# programmer.net
KiCad netlist of a schematic drawn in Altium Designer
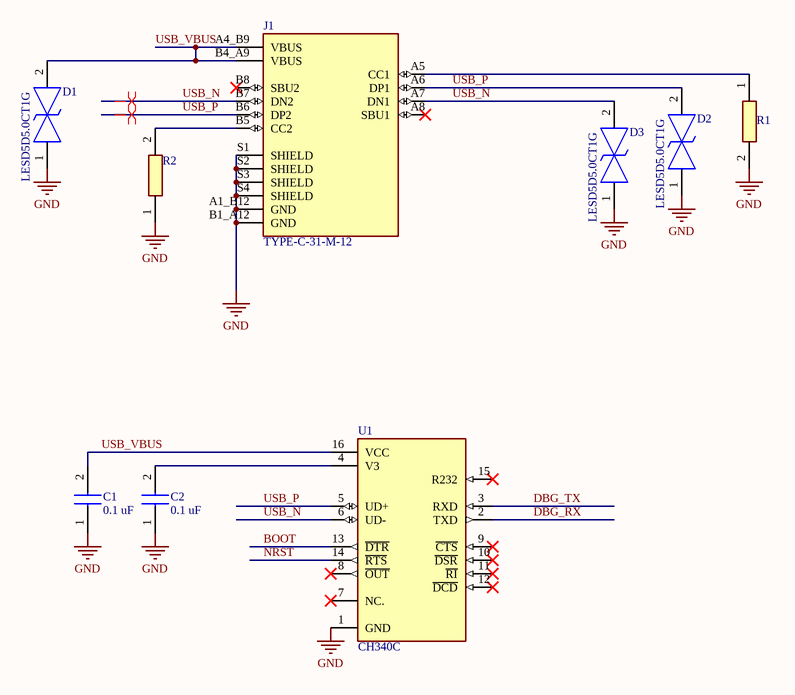
[diagram p0: programmer.SchDoc]

(export (version "E")
  (design (tool "Eeschema 10.0.6"))
  (components
    (comp (ref "C1")
      (value "0.1 uF")
      (footprint "CAP0603")
      (description "Capacitor")
      (fields
        (field (name "MANUFACTURER_PART_NUMBER") "CC0603KRX7R9BB104")
        (field (name "MOUSER PART NUMBER") "603-CC603KRX7R9BB104")
      )
      (libsource (lib "Valve_Controller_Lib") (part "CC0603KRX7R9BB104"))
    )
    (comp (ref "C2")
      (value "0.1 uF")
      (footprint "CAP0603")
      (description "Capacitor")
      (fields
        (field (name "MANUFACTURER_PART_NUMBER") "CC0603KRX7R9BB104")
        (field (name "MOUSER PART NUMBER") "603-CC603KRX7R9BB104")
      )
      (libsource (lib "Valve_Controller_Lib") (part "CC0603KRX7R9BB104"))
    )
    (comp (ref "D1")
      (value "LESD5D5.0CT1G")
      (footprint "SamacSys:LESD5D50CT1G")
      (description "TVS Diode (Bi-directional)")
      (libsource (lib "*") (part "LESD5D5.0CT1G"))
    )
    (comp (ref "D2")
      (value "LESD5D5.0CT1G")
      (footprint "SamacSys:LESD5D50CT1G")
      (description "TVS Diode (Bi-directional)")
      (libsource (lib "*") (part "LESD5D5.0CT1G"))
    )
    (comp (ref "D3")
      (value "LESD5D5.0CT1G")
      (footprint "SamacSys:LESD5D50CT1G")
      (description "TVS Diode (Bi-directional)")
      (libsource (lib "*") (part "LESD5D5.0CT1G"))
    )
    (comp (ref "J1")
      (value "TYPE-C-31-M-12")
      (footprint "HRO_TYPE-C-31-M-12")
      (description "USB Connectors 24 Receptacle 1 8.94*7.3mm RoHS")
      (fields (field (name "MF") "HRO Electronics Co., Ltd."))
      (libsource (lib "TYPE-C-31-M-12") (part "TYPE-C-31-M-12"))
    )
    (comp (ref "R1")
      (value "CRCW0402100KFKEDHP")
      (footprint "RESC1005X40N")
      (description "Resistor")
      (fields (field (name "MOUSER PART NUMBER") "71-CRCW0402100KFKEDH"))
      (libsource (lib "") (part "CRCW0402100KFKEDHP_1"))
    )
    (comp (ref "R2")
      (value "CRCW0402100KFKEDHP")
      (footprint "RESC1005X40N")
      (description "Resistor")
      (fields (field (name "MOUSER PART NUMBER") "71-CRCW0402100KFKEDH"))
      (libsource (lib "Valve_Controller_Lib") (part "CRCW0402100KFKEDHP"))
    )
    (comp (ref "U1")
      (value "CH340C")
      (footprint "SOIC127P600X180-16N")
      (description "USB to serial chip CH340")
      (fields (field (name "MF") "WCH"))
      (libsource (lib "CH340C") (part "CH340C"))
    )
  )
  (nets
    (net (code "1") (name "/BOOT") (class "Default")
      (node (ref "U1") (pin "13") (pinfunction "~{DTR}_13") (pintype "output"))
    )
    (net (code "2") (name "/DBG_RX") (class "Default")
      (node (ref "U1") (pin "2") (pinfunction "TXD_2") (pintype "output"))
    )
    (net (code "3") (name "/DBG_TX") (class "Default")
      (node (ref "U1") (pin "3") (pinfunction "RXD_3") (pintype "input"))
    )
    (net (code "4") (name "/NRST") (class "Default")
      (node (ref "U1") (pin "14") (pinfunction "~{RTS}_14") (pintype "output"))
    )
    (net (code "5") (name "/USB_N") (class "Default")
      (node (ref "D3") (pin "2") (pinfunction "2_2") (pintype "passive"))
      (node (ref "J1") (pin "A7") (pinfunction "DN1_A7") (pintype "bidirectional"))
      (node (ref "J1") (pin "B7") (pinfunction "DN2_B7") (pintype "bidirectional"))
      (node (ref "U1") (pin "6") (pinfunction "UD-_6") (pintype "bidirectional"))
    )
    (net (code "6") (name "/USB_P") (class "Default")
      (node (ref "D2") (pin "2") (pinfunction "2_2") (pintype "passive"))
      (node (ref "J1") (pin "A6") (pinfunction "DP1_A6") (pintype "bidirectional"))
      (node (ref "J1") (pin "B6") (pinfunction "DP2_B6") (pintype "bidirectional"))
      (node (ref "U1") (pin "5") (pinfunction "UD+_5") (pintype "bidirectional"))
    )
    (net (code "7") (name "/USB_VBUS") (class "Default")
      (node (ref "C1") (pin "2") (pinfunction "2_2") (pintype "passive"))
      (node (ref "D1") (pin "2") (pinfunction "2_2") (pintype "passive"))
      (node (ref "J1") (pin "A4_B9") (pinfunction "VBUS_A4_B9") (pintype "power_in"))
      (node (ref "J1") (pin "B4_A9") (pinfunction "VBUS_B4_A9") (pintype "power_in"))
      (node (ref "U1") (pin "16") (pinfunction "VCC_16") (pintype "power_in"))
    )
    (net (code "8") (name "GND") (class "Default")
      (node (ref "C1") (pin "1") (pinfunction "1_1") (pintype "passive"))
      (node (ref "C2") (pin "1") (pinfunction "1_1") (pintype "passive"))
      (node (ref "D1") (pin "1") (pinfunction "1_1") (pintype "passive"))
      (node (ref "D2") (pin "1") (pinfunction "1_1") (pintype "passive"))
      (node (ref "D3") (pin "1") (pinfunction "1_1") (pintype "passive"))
      (node (ref "J1") (pin "A1_B12") (pinfunction "GND_A1_B12") (pintype "power_in"))
      (node (ref "J1") (pin "B1_A12") (pinfunction "GND_B1_A12") (pintype "power_in"))
      (node (ref "J1") (pin "S1") (pinfunction "SHIELD_S1") (pintype "passive"))
      (node (ref "J1") (pin "S2") (pinfunction "SHIELD_S2") (pintype "passive"))
      (node (ref "J1") (pin "S3") (pinfunction "SHIELD_S3") (pintype "passive"))
      (node (ref "J1") (pin "S4") (pinfunction "SHIELD_S4") (pintype "passive"))
      (node (ref "R1") (pin "2") (pinfunction "2_2") (pintype "passive"))
      (node (ref "R2") (pin "1") (pinfunction "1_1") (pintype "passive"))
      (node (ref "U1") (pin "1") (pinfunction "GND_1") (pintype "power_in"))
    )
    (net (code "9") (name "Net-(J1-CC1)") (class "Default")
      (node (ref "J1") (pin "A5") (pinfunction "CC1_A5") (pintype "bidirectional"))
      (node (ref "R1") (pin "1") (pinfunction "1_1") (pintype "passive"))
    )
    (net (code "10") (name "Net-(J1-CC2)") (class "Default")
      (node (ref "J1") (pin "B5") (pinfunction "CC2_B5") (pintype "bidirectional"))
      (node (ref "R2") (pin "2") (pinfunction "2_2") (pintype "passive"))
    )
    (net (code "11") (name "Net-(U1-V3)") (class "Default")
      (node (ref "C2") (pin "2") (pinfunction "2_2") (pintype "passive"))
      (node (ref "U1") (pin "4") (pinfunction "V3_4") (pintype "power_in"))
    )
    (net (code "12") (name "unconnected-(J1-SBU1-PadA8)") (class "Default")
      (node (ref "J1") (pin "A8") (pinfunction "SBU1_A8") (pintype "bidirectional+no_connect"))
    )
    (net (code "13") (name "unconnected-(J1-SBU2-PadB8)") (class "Default")
      (node (ref "J1") (pin "B8") (pinfunction "SBU2_B8") (pintype "bidirectional+no_connect"))
    )
    (net (code "14") (name "unconnected-(U1-NC.-Pad7)") (class "Default")
      (node (ref "U1") (pin "7") (pinfunction "NC._7") (pintype "passive+no_connect"))
    )
    (net (code "15") (name "unconnected-(U1-R232-Pad15)") (class "Default")
      (node (ref "U1") (pin "15") (pinfunction "R232_15") (pintype "input+no_connect"))
    )
    (net (code "16") (name "unconnected-(U1-~{CTS}-Pad9)") (class "Default")
      (node (ref "U1") (pin "9") (pinfunction "~{CTS}_9") (pintype "input+no_connect"))
    )
    (net (code "17") (name "unconnected-(U1-~{DCD}-Pad12)") (class "Default")
      (node (ref "U1") (pin "12") (pinfunction "~{DCD}_12") (pintype "input+no_connect"))
    )
    (net (code "18") (name "unconnected-(U1-~{DSR}-Pad10)") (class "Default")
      (node (ref "U1") (pin "10") (pinfunction "~{DSR}_10") (pintype "input+no_connect"))
    )
    (net (code "19") (name "unconnected-(U1-~{OUT}-Pad8)") (class "Default")
      (node (ref "U1") (pin "8") (pinfunction "~{OUT}_8") (pintype "output+no_connect"))
    )
    (net (code "20") (name "unconnected-(U1-~{RI}-Pad11)") (class "Default")
      (node (ref "U1") (pin "11") (pinfunction "~{RI}_11") (pintype "input+no_connect"))
    )
  )
)
